# ai_breakout_LSM9DS0.net
KiCad netlist of a schematic drawn in EAGLE
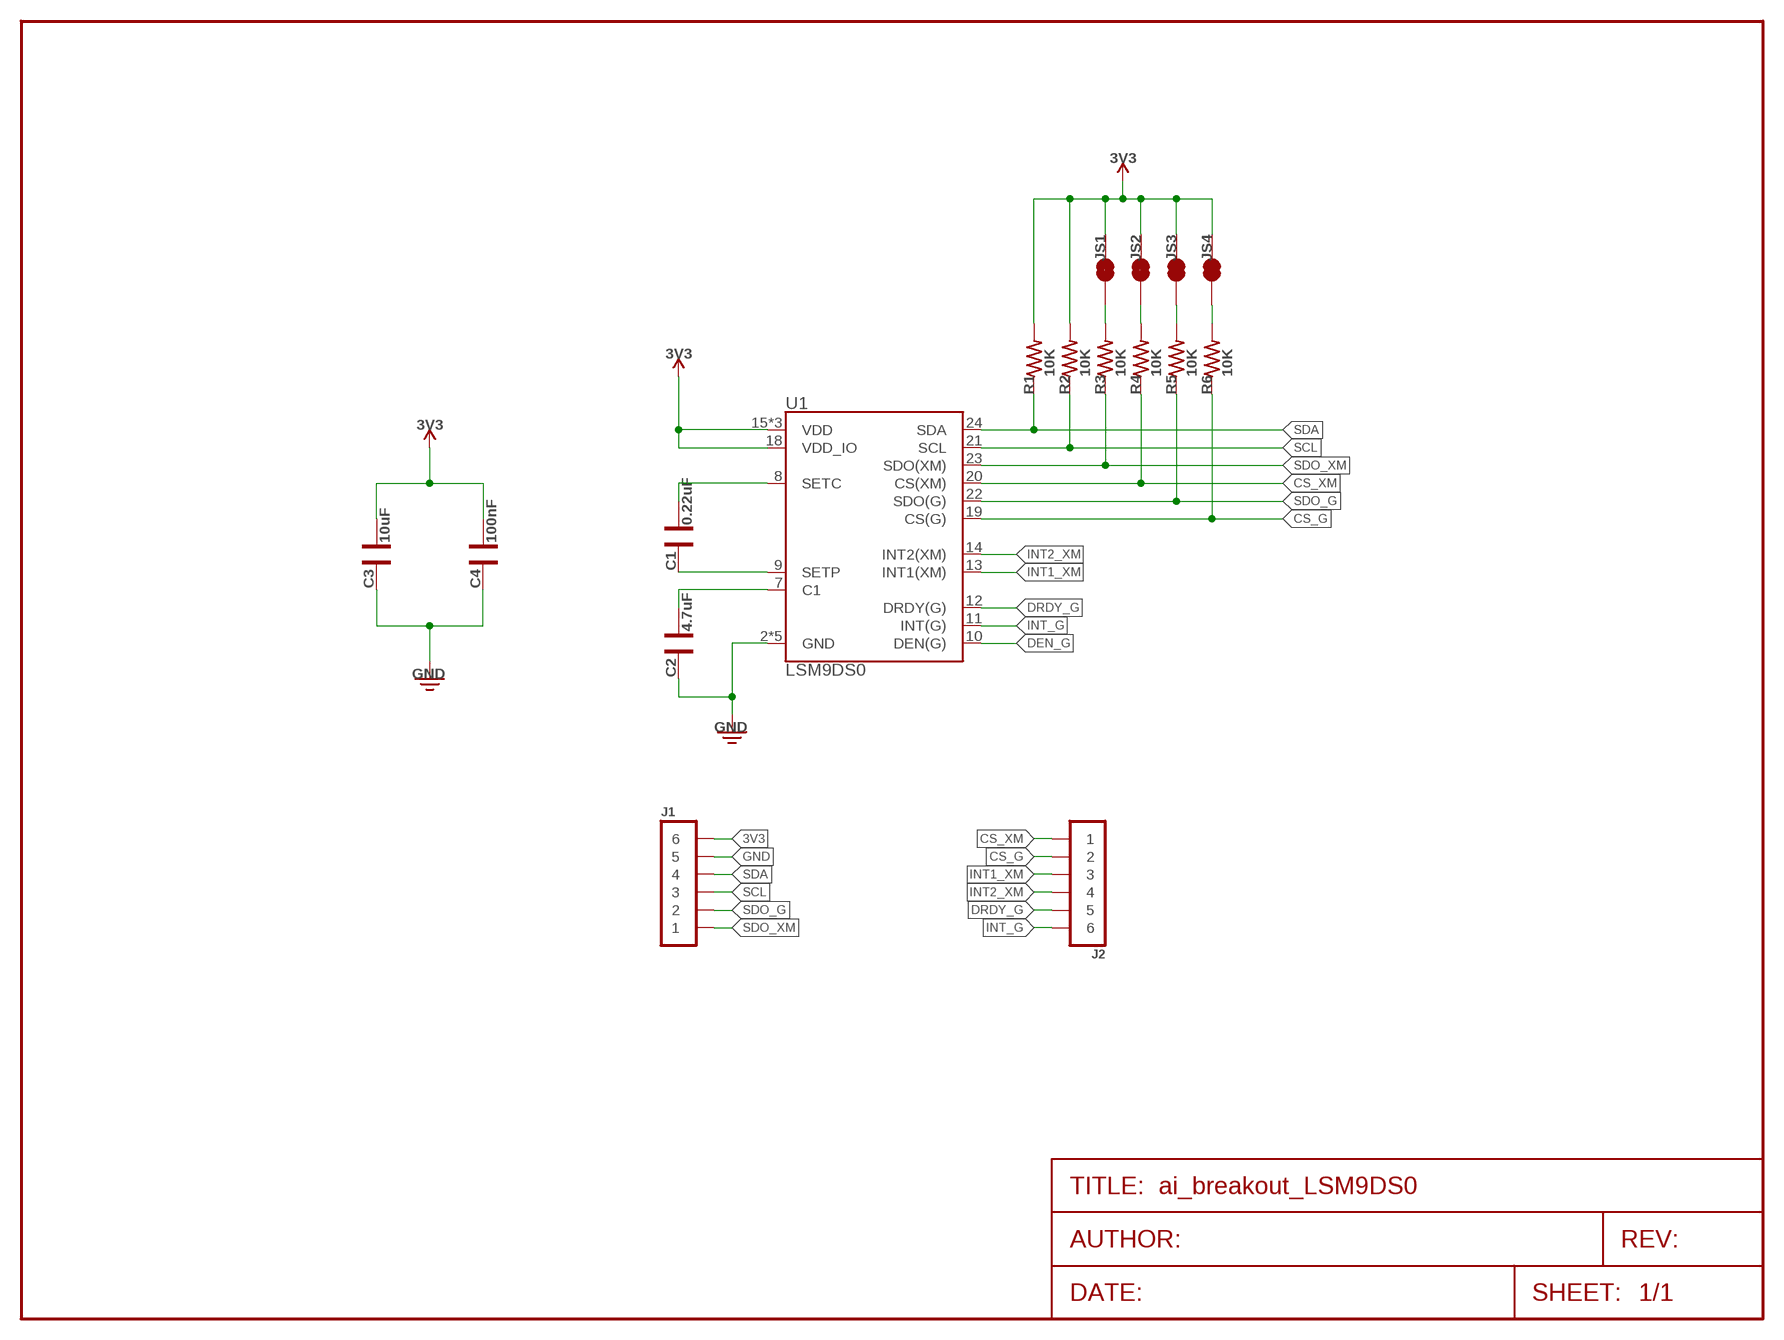
[diagram p0: schematic, sheet 1]

(export (version "E")
  (design (tool "Eeschema 10.0.6"))
  (components
    (comp (ref "C1")
      (value "0.22uF")
      (footprint "eagle-import:CAP-0603")
      (libsource (lib "eagle-import") (part "CAP0603"))
    )
    (comp (ref "C2")
      (value "4.7uF")
      (footprint "eagle-import:CAP-0603")
      (libsource (lib "eagle-import") (part "CAP0603"))
    )
    (comp (ref "C3")
      (value "10uF")
      (footprint "eagle-import:CAP-0603")
      (libsource (lib "eagle-import") (part "CAP0603"))
    )
    (comp (ref "C4")
      (value "100nF")
      (footprint "eagle-import:CAP-0603")
      (libsource (lib "eagle-import") (part "CAP0603"))
    )
    (comp (ref "J1")
      (value "1X06")
      (footprint "eagle-import:1X06")
      (libsource (lib "eagle-import") (part "1X06"))
    )
    (comp (ref "J2")
      (value "1X06")
      (footprint "eagle-import:1X06")
      (libsource (lib "eagle-import") (part "1X06"))
    )
    (comp (ref "JS1")
      (value "1X02-SJ-NCT")
      (footprint "eagle-import:1X02-SJ-NCT")
      (libsource (lib "eagle-import") (part "1X02-SJ-NCT"))
    )
    (comp (ref "JS2")
      (value "1X02-SJ-NCT")
      (footprint "eagle-import:1X02-SJ-NCT")
      (libsource (lib "eagle-import") (part "1X02-SJ-NCT"))
    )
    (comp (ref "JS3")
      (value "1X02-SJ-NCT")
      (footprint "eagle-import:1X02-SJ-NCT")
      (libsource (lib "eagle-import") (part "1X02-SJ-NCT"))
    )
    (comp (ref "JS4")
      (value "1X02-SJ-NCT")
      (footprint "eagle-import:1X02-SJ-NCT")
      (libsource (lib "eagle-import") (part "1X02-SJ-NCT"))
    )
    (comp (ref "R1")
      (value "10K")
      (footprint "eagle-import:RES-0603")
      (libsource (lib "eagle-import") (part "RES0603"))
    )
    (comp (ref "R2")
      (value "10K")
      (footprint "eagle-import:RES-0603")
      (libsource (lib "eagle-import") (part "RES0603"))
    )
    (comp (ref "R3")
      (value "10K")
      (footprint "eagle-import:RES-0603")
      (libsource (lib "eagle-import") (part "RES0603"))
    )
    (comp (ref "R4")
      (value "10K")
      (footprint "eagle-import:RES-0603")
      (libsource (lib "eagle-import") (part "RES0603"))
    )
    (comp (ref "R5")
      (value "10K")
      (footprint "eagle-import:RES-0603")
      (libsource (lib "eagle-import") (part "RES0603"))
    )
    (comp (ref "R6")
      (value "10K")
      (footprint "eagle-import:RES-0603")
      (libsource (lib "eagle-import") (part "RES0603"))
    )
    (comp (ref "U1")
      (value "LSM9DS0")
      (footprint "eagle-import:LGA-24")
      (libsource (lib "eagle-import") (part "LSM9DS0"))
    )
  )
  (nets
    (net (code "1") (name "3V3") (class "Default")
      (node (ref "C3") (pin "1") (pinfunction "1_1") (pintype "passive"))
      (node (ref "C4") (pin "1") (pinfunction "1_1") (pintype "passive"))
      (node (ref "J1") (pin "6") (pinfunction "6_6") (pintype "bidirectional"))
      (node (ref "JS1") (pin "2") (pinfunction "2_2") (pintype "passive"))
      (node (ref "JS2") (pin "2") (pinfunction "2_2") (pintype "passive"))
      (node (ref "JS3") (pin "2") (pinfunction "2_2") (pintype "passive"))
      (node (ref "JS4") (pin "2") (pinfunction "2_2") (pintype "passive"))
      (node (ref "R1") (pin "2") (pinfunction "2_2") (pintype "passive"))
      (node (ref "R2") (pin "2") (pinfunction "2_2") (pintype "passive"))
      (node (ref "U1") (pin "15") (pinfunction "VDD_15") (pintype "bidirectional"))
      (node (ref "U1") (pin "16") (pinfunction "VDD_16") (pintype "bidirectional"))
      (node (ref "U1") (pin "17") (pinfunction "VDD_17") (pintype "bidirectional"))
      (node (ref "U1") (pin "18") (pinfunction "VDD_IO_18") (pintype "bidirectional"))
    )
    (net (code "2") (name "CS_G") (class "Default")
      (node (ref "J2") (pin "2") (pinfunction "2_2") (pintype "bidirectional"))
      (node (ref "R6") (pin "1") (pinfunction "1_1") (pintype "passive"))
      (node (ref "U1") (pin "19") (pinfunction "CS(G)_19") (pintype "bidirectional"))
    )
    (net (code "3") (name "CS_XM") (class "Default")
      (node (ref "J2") (pin "1") (pinfunction "1_1") (pintype "bidirectional"))
      (node (ref "R4") (pin "1") (pinfunction "1_1") (pintype "passive"))
      (node (ref "U1") (pin "20") (pinfunction "CS(XM)_20") (pintype "bidirectional"))
    )
    (net (code "4") (name "DEN_G") (class "Default")
      (node (ref "U1") (pin "10") (pinfunction "DEN(G)_10") (pintype "bidirectional"))
    )
    (net (code "5") (name "DRDY_G") (class "Default")
      (node (ref "J2") (pin "5") (pinfunction "5_5") (pintype "bidirectional"))
      (node (ref "U1") (pin "12") (pinfunction "DRDY(G)_12") (pintype "bidirectional"))
    )
    (net (code "6") (name "GND") (class "Default")
      (node (ref "C2") (pin "2") (pinfunction "2_2") (pintype "passive"))
      (node (ref "C3") (pin "2") (pinfunction "2_2") (pintype "passive"))
      (node (ref "C4") (pin "2") (pinfunction "2_2") (pintype "passive"))
      (node (ref "J1") (pin "5") (pinfunction "5_5") (pintype "bidirectional"))
      (node (ref "U1") (pin "2") (pinfunction "GND_2") (pintype "bidirectional"))
      (node (ref "U1") (pin "3") (pinfunction "GND_3") (pintype "bidirectional"))
      (node (ref "U1") (pin "4") (pinfunction "GND_4") (pintype "bidirectional"))
      (node (ref "U1") (pin "5") (pinfunction "GND_5") (pintype "bidirectional"))
      (node (ref "U1") (pin "6") (pinfunction "GND_6") (pintype "bidirectional"))
    )
    (net (code "7") (name "INT1_XM") (class "Default")
      (node (ref "J2") (pin "3") (pinfunction "3_3") (pintype "bidirectional"))
      (node (ref "U1") (pin "13") (pinfunction "INT1(XM)_13") (pintype "bidirectional"))
    )
    (net (code "8") (name "INT2_XM") (class "Default")
      (node (ref "J2") (pin "4") (pinfunction "4_4") (pintype "bidirectional"))
      (node (ref "U1") (pin "14") (pinfunction "INT2(XM)_14") (pintype "bidirectional"))
    )
    (net (code "9") (name "INT_G") (class "Default")
      (node (ref "J2") (pin "6") (pinfunction "6_6") (pintype "bidirectional"))
      (node (ref "U1") (pin "11") (pinfunction "INT(G)_11") (pintype "bidirectional"))
    )
    (net (code "10") (name "Net-(JS1-Pad1)") (class "Default")
      (node (ref "JS1") (pin "1") (pinfunction "1_1") (pintype "passive"))
      (node (ref "R3") (pin "2") (pinfunction "2_2") (pintype "passive"))
    )
    (net (code "11") (name "Net-(JS2-Pad1)") (class "Default")
      (node (ref "JS2") (pin "1") (pinfunction "1_1") (pintype "passive"))
      (node (ref "R4") (pin "2") (pinfunction "2_2") (pintype "passive"))
    )
    (net (code "12") (name "Net-(JS3-Pad1)") (class "Default")
      (node (ref "JS3") (pin "1") (pinfunction "1_1") (pintype "passive"))
      (node (ref "R5") (pin "2") (pinfunction "2_2") (pintype "passive"))
    )
    (net (code "13") (name "Net-(JS4-Pad1)") (class "Default")
      (node (ref "JS4") (pin "1") (pinfunction "1_1") (pintype "passive"))
      (node (ref "R6") (pin "2") (pinfunction "2_2") (pintype "passive"))
    )
    (net (code "14") (name "Net-(U1-C1)") (class "Default")
      (node (ref "C2") (pin "1") (pinfunction "1_1") (pintype "passive"))
      (node (ref "U1") (pin "7") (pinfunction "C1_7") (pintype "bidirectional"))
    )
    (net (code "15") (name "Net-(U1-SETC)") (class "Default")
      (node (ref "C1") (pin "1") (pinfunction "1_1") (pintype "passive"))
      (node (ref "U1") (pin "8") (pinfunction "SETC_8") (pintype "bidirectional"))
    )
    (net (code "16") (name "Net-(U1-SETP)") (class "Default")
      (node (ref "C1") (pin "2") (pinfunction "2_2") (pintype "passive"))
      (node (ref "U1") (pin "9") (pinfunction "SETP_9") (pintype "bidirectional"))
    )
    (net (code "17") (name "SCL") (class "Default")
      (node (ref "J1") (pin "3") (pinfunction "3_3") (pintype "bidirectional"))
      (node (ref "R2") (pin "1") (pinfunction "1_1") (pintype "passive"))
      (node (ref "U1") (pin "21") (pinfunction "SCL_21") (pintype "bidirectional"))
    )
    (net (code "18") (name "SDA") (class "Default")
      (node (ref "J1") (pin "4") (pinfunction "4_4") (pintype "bidirectional"))
      (node (ref "R1") (pin "1") (pinfunction "1_1") (pintype "passive"))
      (node (ref "U1") (pin "24") (pinfunction "SDA_24") (pintype "bidirectional"))
    )
    (net (code "19") (name "SDO_G") (class "Default")
      (node (ref "J1") (pin "2") (pinfunction "2_2") (pintype "bidirectional"))
      (node (ref "R5") (pin "1") (pinfunction "1_1") (pintype "passive"))
      (node (ref "U1") (pin "22") (pinfunction "SDO(G)_22") (pintype "bidirectional"))
    )
    (net (code "20") (name "SDO_XM") (class "Default")
      (node (ref "J1") (pin "1") (pinfunction "1_1") (pintype "bidirectional"))
      (node (ref "R3") (pin "1") (pinfunction "1_1") (pintype "passive"))
      (node (ref "U1") (pin "23") (pinfunction "SDO(XM)_23") (pintype "bidirectional"))
    )
  )
)
